# MicroPlayerSCH.net
KiCad netlist of a schematic drawn in Altium Designer
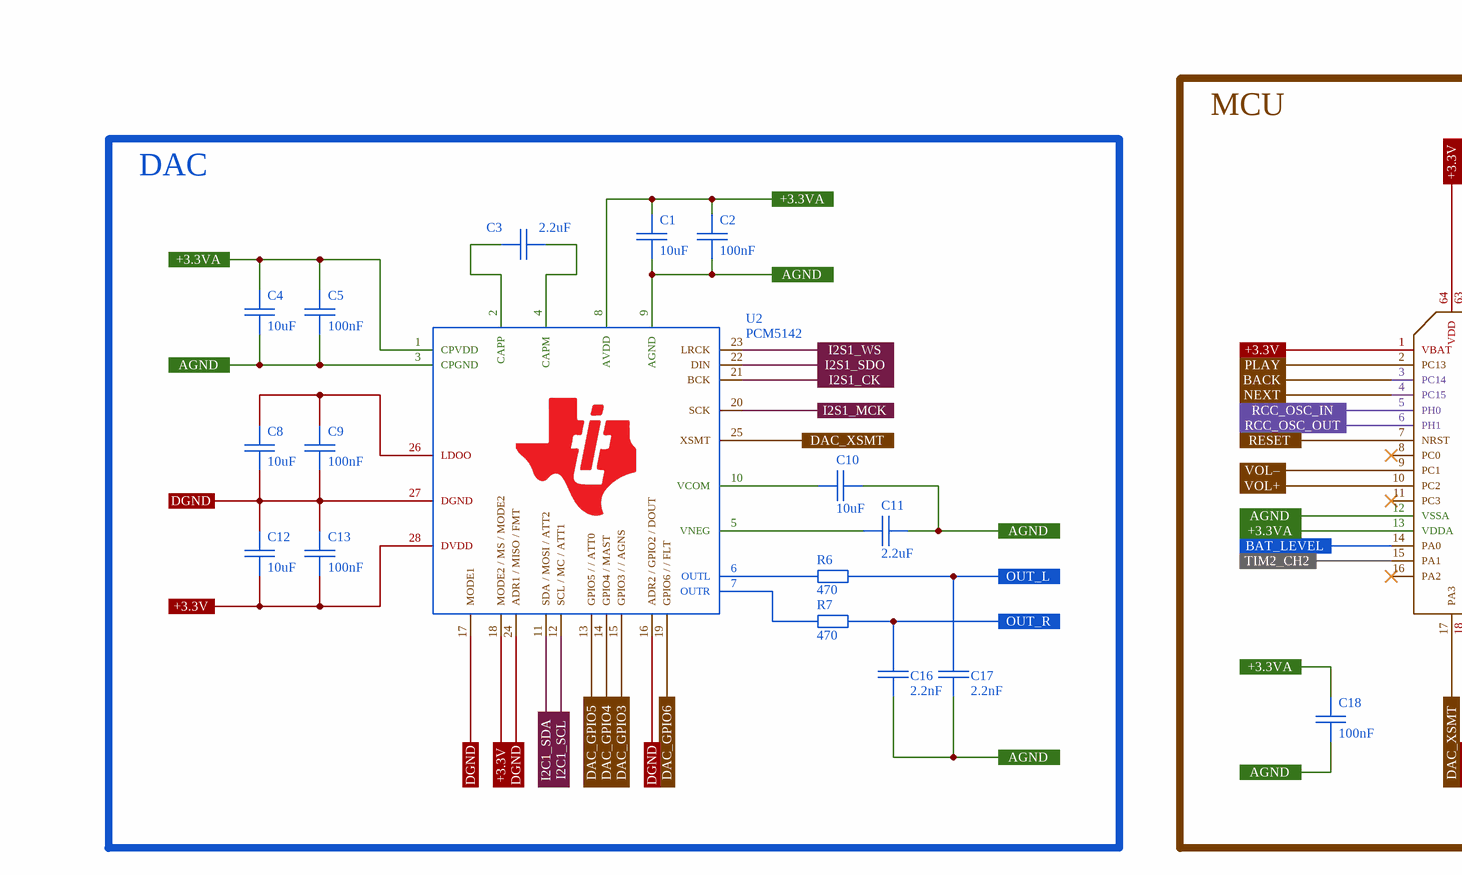
[diagram p0: MicroPlayerSCH.SchDoc, top left]
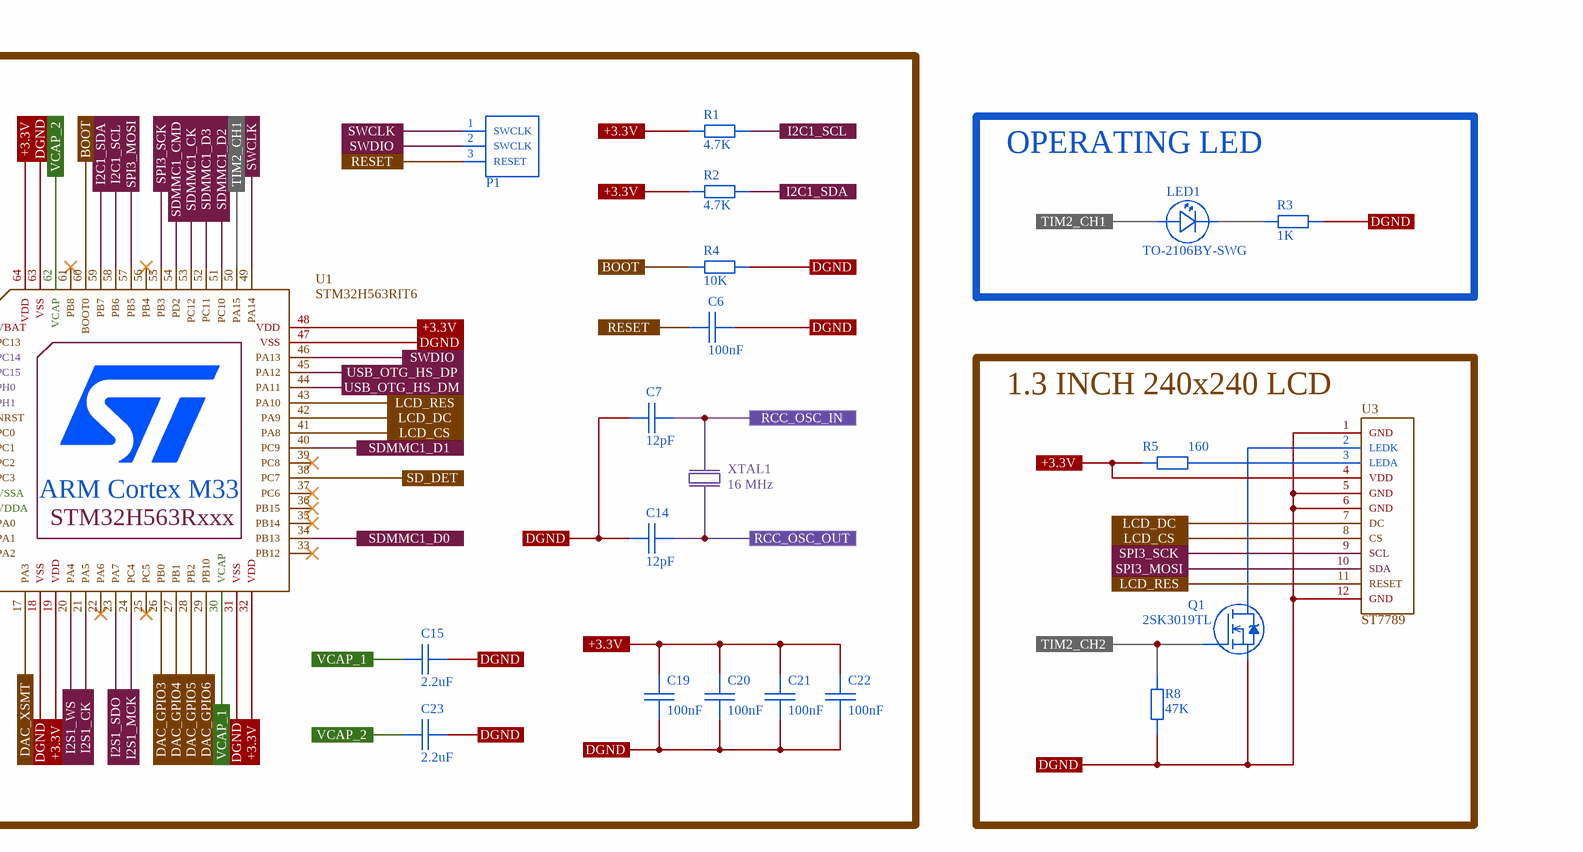
[diagram p1: MicroPlayerSCH.SchDoc, top right]
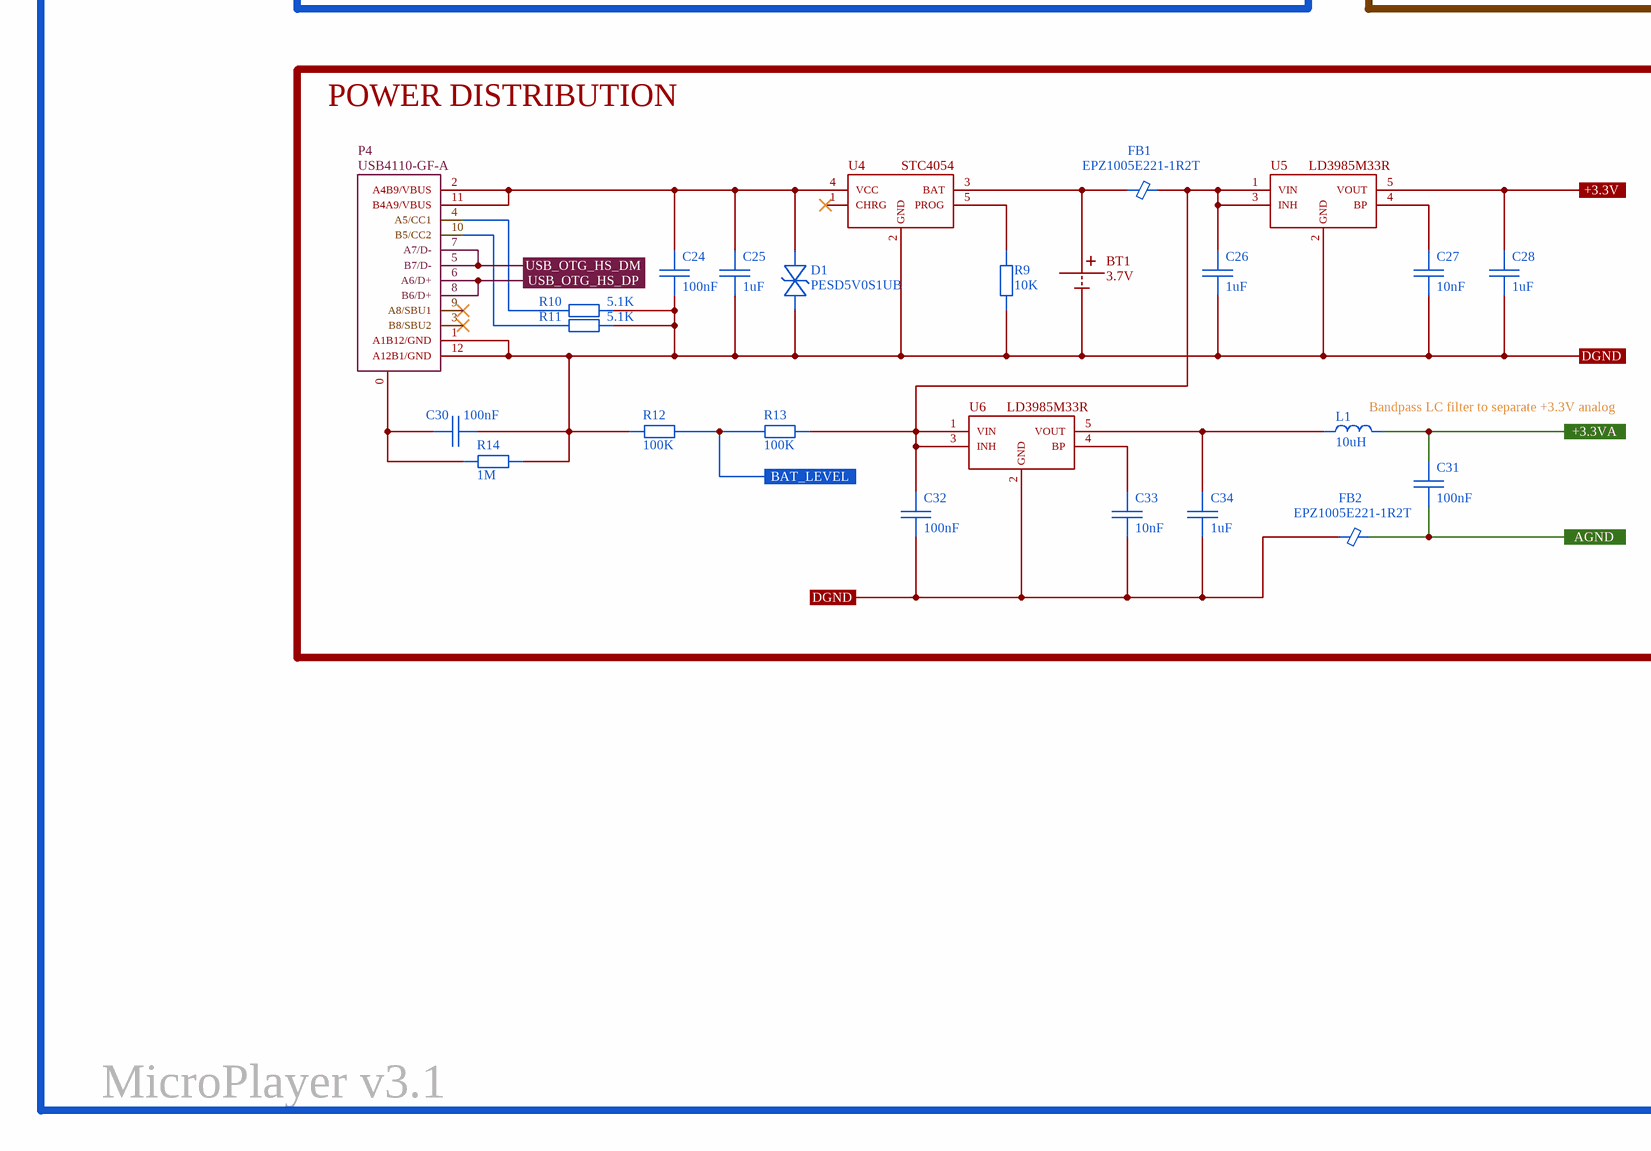
[diagram p2: MicroPlayerSCH.SchDoc, bottom left]
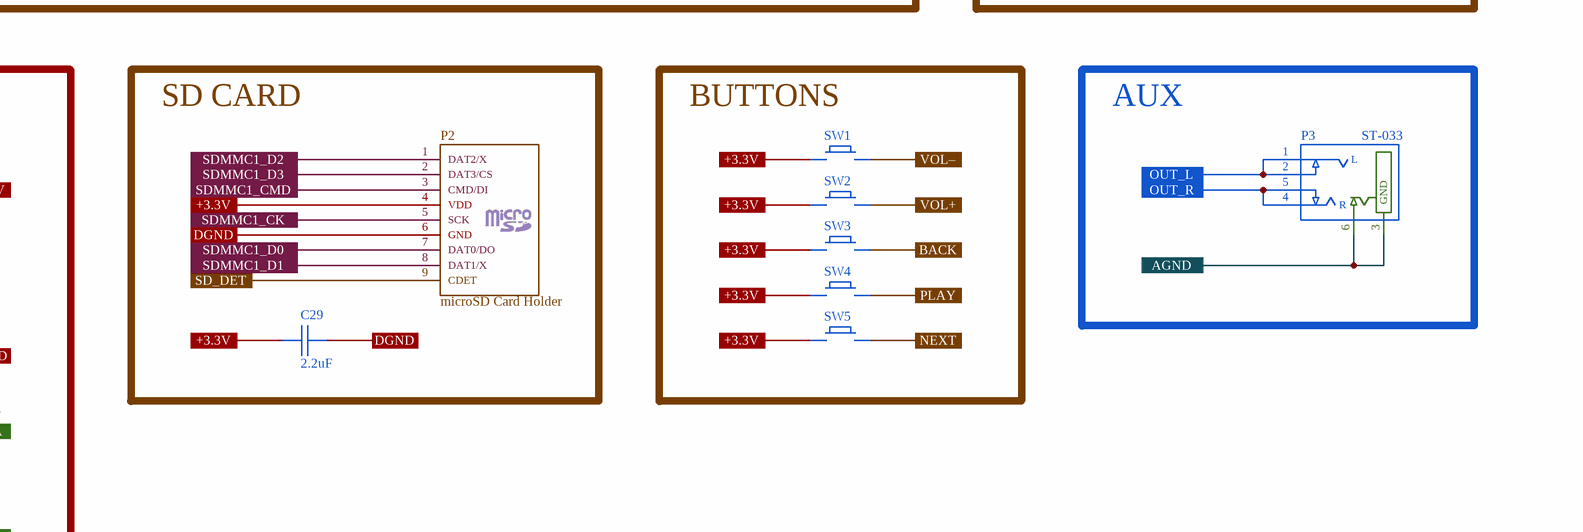
[diagram p3: MicroPlayerSCH.SchDoc, bottom right]

(export (version "E")
  (design (tool "Eeschema 10.0.6"))
  (components
    (comp (ref "BT1") (value "3.7V") (footprint "_2-PAD-SM") (libsource (lib "PowerUnits") (part "Battery")))
    (comp (ref "C1")
      (value "10uF")
      (footprint "C0402")
      (fields (field (name "VOLTAGE") "250V") (field (name "TOLERANCE") "5%"))
      (libsource (lib "CommonElements") (part "Cap"))
    )
    (comp (ref "C2")
      (value "100nF")
      (footprint "C0402")
      (fields (field (name "VOLTAGE") "250V") (field (name "TOLERANCE") "5%"))
      (libsource (lib "CommonElements") (part "Cap"))
    )
    (comp (ref "C3")
      (value "2.2uF")
      (footprint "C0402")
      (fields (field (name "VOLTAGE") "250V") (field (name "TOLERANCE") "5%"))
      (libsource (lib "CommonElements") (part "Cap"))
    )
    (comp (ref "C4")
      (value "10uF")
      (footprint "C0402")
      (fields (field (name "VOLTAGE") "250V") (field (name "TOLERANCE") "5%"))
      (libsource (lib "CommonElements") (part "Cap"))
    )
    (comp (ref "C5")
      (value "100nF")
      (footprint "C0402")
      (fields (field (name "VOLTAGE") "250V") (field (name "TOLERANCE") "5%"))
      (libsource (lib "CommonElements") (part "Cap"))
    )
    (comp (ref "C6")
      (value "100nF")
      (footprint "C0402")
      (fields (field (name "VOLTAGE") "250V") (field (name "TOLERANCE") "5%"))
      (libsource (lib "CommonElements") (part "Cap"))
    )
    (comp (ref "C7")
      (value "12pF")
      (footprint "C0402")
      (fields (field (name "VOLTAGE") "250V") (field (name "TOLERANCE") "5%"))
      (libsource (lib "CommonElements") (part "Cap"))
    )
    (comp (ref "C8")
      (value "10uF")
      (footprint "C0402")
      (fields (field (name "VOLTAGE") "250V") (field (name "TOLERANCE") "5%"))
      (libsource (lib "CommonElements") (part "Cap"))
    )
    (comp (ref "C9")
      (value "100nF")
      (footprint "C0402")
      (fields (field (name "VOLTAGE") "250V") (field (name "TOLERANCE") "5%"))
      (libsource (lib "CommonElements") (part "Cap"))
    )
    (comp (ref "C10")
      (value "10uF")
      (footprint "C0402")
      (fields (field (name "VOLTAGE") "250V") (field (name "TOLERANCE") "5%"))
      (libsource (lib "CommonElements") (part "Cap"))
    )
    (comp (ref "C11")
      (value "2.2uF")
      (footprint "C0402")
      (fields (field (name "VOLTAGE") "250V") (field (name "TOLERANCE") "5%"))
      (libsource (lib "CommonElements") (part "Cap"))
    )
    (comp (ref "C12")
      (value "10uF")
      (footprint "C0402")
      (fields (field (name "VOLTAGE") "250V") (field (name "TOLERANCE") "5%"))
      (libsource (lib "CommonElements") (part "Cap"))
    )
    (comp (ref "C13")
      (value "100nF")
      (footprint "C0402")
      (fields (field (name "VOLTAGE") "250V") (field (name "TOLERANCE") "5%"))
      (libsource (lib "CommonElements") (part "Cap"))
    )
    (comp (ref "C14")
      (value "12pF")
      (footprint "C0402")
      (fields (field (name "VOLTAGE") "250V") (field (name "TOLERANCE") "5%"))
      (libsource (lib "CommonElements") (part "Cap"))
    )
    (comp (ref "C15")
      (value "2.2uF")
      (footprint "C0402")
      (fields (field (name "VOLTAGE") "250V") (field (name "TOLERANCE") "5%"))
      (libsource (lib "CommonElements") (part "Cap"))
    )
    (comp (ref "C16")
      (value "2.2nF")
      (footprint "C0402")
      (fields (field (name "VOLTAGE") "250V") (field (name "TOLERANCE") "5%"))
      (libsource (lib "CommonElements") (part "Cap"))
    )
    (comp (ref "C17")
      (value "2.2nF")
      (footprint "C0402")
      (fields (field (name "VOLTAGE") "250V") (field (name "TOLERANCE") "5%"))
      (libsource (lib "CommonElements") (part "Cap"))
    )
    (comp (ref "C18")
      (value "100nF")
      (footprint "C0402")
      (fields (field (name "VOLTAGE") "250V") (field (name "TOLERANCE") "5%"))
      (libsource (lib "CommonElements") (part "Cap"))
    )
    (comp (ref "C19")
      (value "100nF")
      (footprint "C0402")
      (fields (field (name "VOLTAGE") "250V") (field (name "TOLERANCE") "5%"))
      (libsource (lib "CommonElements") (part "Cap"))
    )
    (comp (ref "C20")
      (value "100nF")
      (footprint "C0402")
      (fields (field (name "VOLTAGE") "250V") (field (name "TOLERANCE") "5%"))
      (libsource (lib "CommonElements") (part "Cap"))
    )
    (comp (ref "C21")
      (value "100nF")
      (footprint "C0402")
      (fields (field (name "VOLTAGE") "250V") (field (name "TOLERANCE") "5%"))
      (libsource (lib "CommonElements") (part "Cap"))
    )
    (comp (ref "C22")
      (value "100nF")
      (footprint "C0402")
      (fields (field (name "VOLTAGE") "250V") (field (name "TOLERANCE") "5%"))
      (libsource (lib "CommonElements") (part "Cap"))
    )
    (comp (ref "C23")
      (value "2.2uF")
      (footprint "C0402")
      (fields (field (name "VOLTAGE") "250V") (field (name "TOLERANCE") "5%"))
      (libsource (lib "CommonElements") (part "Cap"))
    )
    (comp (ref "C24")
      (value "100nF")
      (footprint "C0402")
      (fields (field (name "VOLTAGE") "250V") (field (name "TOLERANCE") "5%"))
      (libsource (lib "CommonElements") (part "Cap"))
    )
    (comp (ref "C25")
      (value "1uF")
      (footprint "C0402")
      (fields (field (name "VOLTAGE") "250V") (field (name "TOLERANCE") "5%"))
      (libsource (lib "CommonElements") (part "Cap"))
    )
    (comp (ref "C26")
      (value "1uF")
      (footprint "C0402")
      (fields (field (name "VOLTAGE") "250V") (field (name "TOLERANCE") "5%"))
      (libsource (lib "CommonElements") (part "Cap"))
    )
    (comp (ref "C27")
      (value "10nF")
      (footprint "C0402")
      (fields (field (name "VOLTAGE") "250V") (field (name "TOLERANCE") "5%"))
      (libsource (lib "CommonElements") (part "Cap"))
    )
    (comp (ref "C28")
      (value "1uF")
      (footprint "C0402")
      (fields (field (name "VOLTAGE") "250V") (field (name "TOLERANCE") "5%"))
      (libsource (lib "CommonElements") (part "Cap"))
    )
    (comp (ref "C29")
      (value "2.2uF")
      (footprint "C0402")
      (fields (field (name "VOLTAGE") "250V") (field (name "TOLERANCE") "5%"))
      (libsource (lib "CommonElements") (part "Cap"))
    )
    (comp (ref "C30")
      (value "100nF")
      (footprint "C0402")
      (fields (field (name "VOLTAGE") "250V") (field (name "TOLERANCE") "5%"))
      (libsource (lib "CommonElements") (part "Cap"))
    )
    (comp (ref "C31")
      (value "100nF")
      (footprint "C0402")
      (fields (field (name "VOLTAGE") "250V") (field (name "TOLERANCE") "5%"))
      (libsource (lib "CommonElements") (part "Cap"))
    )
    (comp (ref "C32")
      (value "100nF")
      (footprint "C0402")
      (fields (field (name "VOLTAGE") "250V") (field (name "TOLERANCE") "5%"))
      (libsource (lib "CommonElements") (part "Cap"))
    )
    (comp (ref "C33")
      (value "10nF")
      (footprint "C0402")
      (fields (field (name "VOLTAGE") "250V") (field (name "TOLERANCE") "5%"))
      (libsource (lib "CommonElements") (part "Cap"))
    )
    (comp (ref "C34")
      (value "1uF")
      (footprint "C0402")
      (fields (field (name "VOLTAGE") "250V") (field (name "TOLERANCE") "5%"))
      (libsource (lib "CommonElements") (part "Cap"))
    )
    (comp (ref "D1")
      (value "PESD5V0S1UB")
      (footprint "SOD-523")
      (libsource (lib "CommonElements") (part "Suppressor"))
    )
    (comp (ref "FB1")
      (value "EPZ1005E221-1R2T")
      (footprint "L0402")
      (libsource (lib "CommonElements") (part "Ferrite Bead"))
    )
    (comp (ref "FB2")
      (value "EPZ1005E221-1R2T")
      (footprint "L0402")
      (libsource (lib "CommonElements") (part "Ferrite Bead"))
    )
    (comp (ref "L1")
      (value "10uH")
      (footprint "L0603")
      (fields (field (name "TOLERANCE") "30%") (field (name "PART NUMBER") "LQM21FN100N00K"))
      (libsource (lib "CommonElements") (part "Inductor"))
    )
    (comp (ref "LED1")
      (value "TO-2106BY-SWG")
      (footprint "LED-2106-R/A")
      (libsource (lib "CommonElements") (part "LED"))
    )
    (comp (ref "P1") (value "P3") (footprint "_3-PAD-SM") (libsource (lib "Connectors") (part "P3")))
    (comp (ref "P2")
      (value "microSD Card Holder")
      (footprint "L-KLS1-TF-003")
      (libsource (lib "Connectors") (part "MicroSD-CD1"))
    )
    (comp (ref "P3")
      (value "ST-033")
      (footprint "_3-PAD-TH")
      (libsource (lib "Connectors") (part "AJack Socket Stereo"))
    )
    (comp (ref "P4")
      (value "USB4110-GF-A")
      (footprint "USB-TYPE-C")
      (libsource (lib "Connectors") (part "USB Type C with 0"))
    )
    (comp (ref "Q1")
      (value "2SK3019TL")
      (footprint "SOT-416FL")
      (libsource (lib "CommonElements") (part "MOSFET-N"))
    )
    (comp (ref "R1")
      (value "4.7K")
      (footprint "R0402")
      (fields (field (name "TOLERANCE") "5%") (field (name "POWER") "0.125W"))
      (libsource (lib "CommonElements") (part "Res"))
    )
    (comp (ref "R2")
      (value "4.7K")
      (footprint "R0402")
      (fields (field (name "TOLERANCE") "5%") (field (name "POWER") "0.125W"))
      (libsource (lib "CommonElements") (part "Res"))
    )
    (comp (ref "R3")
      (value "1K")
      (footprint "R0402")
      (fields (field (name "TOLERANCE") "5%") (field (name "POWER") "0.125W"))
      (libsource (lib "CommonElements") (part "Res"))
    )
    (comp (ref "R4")
      (value "10K")
      (footprint "R0402")
      (fields (field (name "TOLERANCE") "5%") (field (name "POWER") "0.125W"))
      (libsource (lib "CommonElements") (part "Res"))
    )
    (comp (ref "R5")
      (value "160")
      (footprint "R0402")
      (fields (field (name "TOLERANCE") "5%") (field (name "POWER") "0.125W"))
      (libsource (lib "CommonElements") (part "Res"))
    )
    (comp (ref "R6")
      (value "470")
      (footprint "R0402")
      (fields (field (name "TOLERANCE") "5%") (field (name "POWER") "0.125W"))
      (libsource (lib "CommonElements") (part "Res"))
    )
    (comp (ref "R7")
      (value "470")
      (footprint "R0402")
      (fields (field (name "TOLERANCE") "5%") (field (name "POWER") "0.125W"))
      (libsource (lib "CommonElements") (part "Res"))
    )
    (comp (ref "R8")
      (value "47K")
      (footprint "R0402")
      (fields (field (name "TOLERANCE") "5%") (field (name "POWER") "0.125W"))
      (libsource (lib "CommonElements") (part "Res"))
    )
    (comp (ref "R9")
      (value "10K")
      (footprint "R0402")
      (fields (field (name "TOLERANCE") "5%") (field (name "POWER") "0.125W"))
      (libsource (lib "CommonElements") (part "Res"))
    )
    (comp (ref "R10")
      (value "5.1K")
      (footprint "R0402")
      (fields (field (name "TOLERANCE") "5%") (field (name "POWER") "0.125W"))
      (libsource (lib "CommonElements") (part "Res"))
    )
    (comp (ref "R11")
      (value "5.1K")
      (footprint "R0402")
      (fields (field (name "TOLERANCE") "5%") (field (name "POWER") "0.125W"))
      (libsource (lib "CommonElements") (part "Res"))
    )
    (comp (ref "R12")
      (value "100K")
      (footprint "R0402")
      (fields (field (name "TOLERANCE") "5%") (field (name "POWER") "0.125W"))
      (libsource (lib "CommonElements") (part "Res"))
    )
    (comp (ref "R13")
      (value "100K")
      (footprint "R0402")
      (fields (field (name "TOLERANCE") "5%") (field (name "POWER") "0.125W"))
      (libsource (lib "CommonElements") (part "Res"))
    )
    (comp (ref "R14")
      (value "1M")
      (footprint "R0402")
      (fields (field (name "TOLERANCE") "5%") (field (name "POWER") "0.125W"))
      (libsource (lib "CommonElements") (part "Res"))
    )
    (comp (ref "SW1")
      (value "~")
      (footprint "BUT-SMD-4X3.5X2MM")
      (libsource (lib "CommonElements") (part "Button"))
    )
    (comp (ref "SW2")
      (value "~")
      (footprint "BUT-SMD-4X3.5X2MM")
      (libsource (lib "CommonElements") (part "Button"))
    )
    (comp (ref "SW3")
      (value "~")
      (footprint "BUT-SMD-4X3.5X2MM")
      (libsource (lib "CommonElements") (part "Button"))
    )
    (comp (ref "SW4")
      (value "~")
      (footprint "BUT-SMD-4X3.5X2MM")
      (libsource (lib "CommonElements") (part "Button"))
    )
    (comp (ref "SW5")
      (value "~")
      (footprint "BUT-SMD-4X3.5X2MM")
      (libsource (lib "CommonElements") (part "Button"))
    )
    (comp (ref "U1")
      (value "STM32H563RIT6")
      (footprint "LQFP64")
      (libsource (lib "STM32") (part "STM32H563Rxxx"))
    )
    (comp (ref "U2")
      (value "PCM5142")
      (footprint "TSSOP28")
      (description "2-VRMS DirectPath™, 112/106-dB Audio Stereo DAC With 32-bit, 384-kHz PCM Interface")
      (libsource (lib "Miscellaneous") (part "PCM514x"))
    )
    (comp (ref "U3")
      (value "ST7789")
      (footprint "1.3INCH_LCD_WELDED")
      (description "135x240 Display")
      (libsource (lib "Modules") (part "1.3inch TFT LCD 12-pin"))
    )
    (comp (ref "U4")
      (value "STC4054")
      (footprint "SOT-23-5")
      (description "800mA Standalone linear Li-Ion Battery charger with thermal regulation")
      (libsource (lib "PowerUnits") (part "STC4054"))
    )
    (comp (ref "U5")
      (value "LD3985M33R")
      (footprint "SOT-23-5")
      (description "Ultra low drop and low noise BiCMOS voltage regulators, 150 mA")
      (libsource (lib "PowerUnits") (part "LD3985"))
    )
    (comp (ref "U6")
      (value "LD3985M33R")
      (footprint "SOT-23-5")
      (description "Ultra low drop and low noise BiCMOS voltage regulators, 150 mA")
      (libsource (lib "PowerUnits") (part "LD3985"))
    )
    (comp (ref "XTAL1")
      (value "16 MHz")
      (footprint "7U")
      (fields (field (name "TOLERANCE") "0.001%"))
      (libsource (lib "CommonElements") (part "Crystal"))
    )
  )
  (nets
    (net (code "1") (name "/+3.3V") (class "Default")
      (node (ref "C12") (pin "2") (pintype "passive"))
      (node (ref "C13") (pin "2") (pintype "passive"))
      (node (ref "C19") (pin "2") (pintype "passive"))
      (node (ref "C20") (pin "2") (pintype "passive"))
      (node (ref "C21") (pin "2") (pintype "passive"))
      (node (ref "C22") (pin "2") (pintype "passive"))
      (node (ref "C28") (pin "2") (pintype "passive"))
      (node (ref "C29") (pin "1") (pintype "passive"))
      (node (ref "P2") (pin "4") (pinfunction "VDD_4") (pintype "passive"))
      (node (ref "R1") (pin "1") (pintype "passive"))
      (node (ref "R2") (pin "1") (pintype "passive"))
      (node (ref "R5") (pin "1") (pintype "passive"))
      (node (ref "SW1") (pin "1") (pintype "passive"))
      (node (ref "SW2") (pin "1") (pintype "passive"))
      (node (ref "SW3") (pin "1") (pintype "passive"))
      (node (ref "SW4") (pin "1") (pintype "passive"))
      (node (ref "SW5") (pin "1") (pintype "passive"))
      (node (ref "U1") (pin "1") (pinfunction "VBAT_1") (pintype "passive"))
      (node (ref "U1") (pin "19") (pinfunction "VDD_19") (pintype "passive"))
      (node (ref "U1") (pin "32") (pinfunction "VDD_32") (pintype "passive"))
      (node (ref "U1") (pin "48") (pinfunction "VDD_48") (pintype "passive"))
      (node (ref "U1") (pin "64") (pinfunction "VDD_64") (pintype "passive"))
      (node (ref "U2") (pin "18") (pinfunction "MODE2_/_MS_/_MODE2_18") (pintype "passive"))
      (node (ref "U2") (pin "28") (pinfunction "DVDD_28") (pintype "passive"))
      (node (ref "U3") (pin "4") (pinfunction "VDD_4") (pintype "passive"))
      (node (ref "U5") (pin "5") (pinfunction "VOUT_5") (pintype "passive"))
    )
    (net (code "2") (name "/+3.3VA") (class "Default")
      (node (ref "C1") (pin "1") (pintype "passive"))
      (node (ref "C18") (pin "2") (pintype "passive"))
      (node (ref "C2") (pin "1") (pintype "passive"))
      (node (ref "C31") (pin "1") (pintype "passive"))
      (node (ref "C4") (pin "1") (pintype "passive"))
      (node (ref "C5") (pin "1") (pintype "passive"))
      (node (ref "L1") (pin "2") (pintype "passive"))
      (node (ref "U1") (pin "13") (pinfunction "VDDA_13") (pintype "passive"))
      (node (ref "U2") (pin "1") (pinfunction "CPVDD_1") (pintype "passive"))
      (node (ref "U2") (pin "8") (pinfunction "AVDD_8") (pintype "passive"))
    )
    (net (code "3") (name "/AGND") (class "Default")
      (node (ref "C1") (pin "2") (pintype "passive"))
      (node (ref "C10") (pin "2") (pintype "passive"))
      (node (ref "C11") (pin "2") (pintype "passive"))
      (node (ref "C16") (pin "1") (pintype "passive"))
      (node (ref "C17") (pin "1") (pintype "passive"))
      (node (ref "C18") (pin "1") (pintype "passive"))
      (node (ref "C2") (pin "2") (pintype "passive"))
      (node (ref "C31") (pin "2") (pintype "passive"))
      (node (ref "C4") (pin "2") (pintype "passive"))
      (node (ref "C5") (pin "2") (pintype "passive"))
      (node (ref "FB2") (pin "2") (pintype "passive"))
      (node (ref "P3") (pin "3") (pinfunction "GND_3") (pintype "passive"))
      (node (ref "P3") (pin "6") (pintype "passive"))
      (node (ref "U1") (pin "12") (pinfunction "VSSA_12") (pintype "passive"))
      (node (ref "U2") (pin "3") (pinfunction "CPGND_3") (pintype "passive"))
      (node (ref "U2") (pin "9") (pinfunction "AGND_9") (pintype "passive"))
    )
    (net (code "4") (name "/BACK") (class "Default")
      (node (ref "SW3") (pin "2") (pintype "passive"))
      (node (ref "U1") (pin "3") (pinfunction "PC14_3") (pintype "passive"))
    )
    (net (code "5") (name "/BAT_LEVEL") (class "Default")
      (node (ref "R12") (pin "1") (pintype "passive"))
      (node (ref "R13") (pin "2") (pintype "passive"))
      (node (ref "U1") (pin "14") (pinfunction "PA0_14") (pintype "passive"))
    )
    (net (code "6") (name "/BOOT") (class "Default")
      (node (ref "R4") (pin "1") (pintype "passive"))
      (node (ref "U1") (pin "60") (pinfunction "BOOT0_60") (pintype "passive"))
    )
    (net (code "7") (name "/DAC_GPIO3") (class "Default")
      (node (ref "U1") (pin "26") (pinfunction "PB0_26") (pintype "passive"))
      (node (ref "U2") (pin "15") (pinfunction "GPIO3_/_/_AGNS_15") (pintype "passive"))
    )
    (net (code "8") (name "/DAC_GPIO4") (class "Default")
      (node (ref "U1") (pin "27") (pinfunction "PB1_27") (pintype "passive"))
      (node (ref "U2") (pin "14") (pinfunction "GPIO4_/_MAST_14") (pintype "passive"))
    )
    (net (code "9") (name "/DAC_GPIO5") (class "Default")
      (node (ref "U1") (pin "28") (pinfunction "PB2_28") (pintype "passive"))
      (node (ref "U2") (pin "13") (pinfunction "GPIO5_/_/_ATT0_13") (pintype "passive"))
    )
    (net (code "10") (name "/DAC_GPIO6") (class "Default")
      (node (ref "U1") (pin "29") (pinfunction "PB10_29") (pintype "passive"))
      (node (ref "U2") (pin "19") (pinfunction "GPIO6_/_/_FLT_19") (pintype "passive"))
    )
    (net (code "11") (name "/DAC_XSMT") (class "Default")
      (node (ref "U1") (pin "17") (pinfunction "PA3_17") (pintype "passive"))
      (node (ref "U2") (pin "25") (pinfunction "XSMT_25") (pintype "passive"))
    )
    (net (code "12") (name "/DGND") (class "Default")
      (node (ref "BT1") (pin "2") (pintype "passive"))
      (node (ref "C12") (pin "1") (pintype "passive"))
      (node (ref "C13") (pin "1") (pintype "passive"))
      (node (ref "C14") (pin "2") (pintype "passive"))
      (node (ref "C15") (pin "1") (pintype "passive"))
      (node (ref "C19") (pin "1") (pintype "passive"))
      (node (ref "C20") (pin "1") (pintype "passive"))
      (node (ref "C21") (pin "1") (pintype "passive"))
      (node (ref "C22") (pin "1") (pintype "passive"))
      (node (ref "C23") (pin "1") (pintype "passive"))
      (node (ref "C24") (pin "1") (pintype "passive"))
      (node (ref "C25") (pin "2") (pintype "passive"))
      (node (ref "C26") (pin "1") (pintype "passive"))
      (node (ref "C27") (pin "1") (pintype "passive"))
      (node (ref "C28") (pin "1") (pintype "passive"))
      (node (ref "C29") (pin "2") (pintype "passive"))
      (node (ref "C30") (pin "1") (pintype "passive"))
      (node (ref "C32") (pin "1") (pintype "passive"))
      (node (ref "C33") (pin "1") (pintype "passive"))
      (node (ref "C34") (pin "1") (pintype "passive"))
      (node (ref "C6") (pin "1") (pintype "passive"))
      (node (ref "C7") (pin "2") (pintype "passive"))
      (node (ref "C8") (pin "2") (pintype "passive"))
      (node (ref "C9") (pin "2") (pintype "passive"))
      (node (ref "D1") (pin "1") (pintype "passive"))
      (node (ref "FB2") (pin "1") (pintype "passive"))
      (node (ref "P2") (pin "6") (pinfunction "GND_6") (pintype "passive"))
      (node (ref "P4") (pin "1") (pinfunction "A1B12/GND_1") (pintype "passive"))
      (node (ref "P4") (pin "12") (pinfunction "A12B1/GND_12") (pintype "passive"))
      (node (ref "Q1") (pin "2") (pinfunction "S_2") (pintype "passive"))
      (node (ref "R10") (pin "1") (pintype "passive"))
      (node (ref "R11") (pin "1") (pintype "passive"))
      (node (ref "R12") (pin "2") (pintype "passive"))
      (node (ref "R14") (pin "1") (pintype "passive"))
      (node (ref "R3") (pin "1") (pintype "passive"))
      (node (ref "R4") (pin "2") (pintype "passive"))
      (node (ref "R8") (pin "1") (pintype "passive"))
      (node (ref "R9") (pin "1") (pintype "passive"))
      (node (ref "U1") (pin "18") (pinfunction "VSS_18") (pintype "passive"))
      (node (ref "U1") (pin "31") (pinfunction "VSS_31") (pintype "passive"))
      (node (ref "U1") (pin "47") (pinfunction "VSS_47") (pintype "passive"))
      (node (ref "U1") (pin "63") (pinfunction "VSS_63") (pintype "passive"))
      (node (ref "U2") (pin "16") (pinfunction "ADR2_/_GPIO2_/_DOUT_16") (pintype "passive"))
      (node (ref "U2") (pin "17") (pinfunction "MODE1_17") (pintype "passive"))
      (node (ref "U2") (pin "24") (pinfunction "ADR1_/_MISO_/_FMT_24") (pintype "passive"))
      (node (ref "U2") (pin "27") (pinfunction "DGND_27") (pintype "passive"))
      (node (ref "U3") (pin "1") (pinfunction "GND_1") (pintype "passive"))
      (node (ref "U3") (pin "12") (pinfunction "GND_12") (pintype "passive"))
      (node (ref "U3") (pin "5") (pinfunction "GND_5") (pintype "passive"))
      (node (ref "U3") (pin "6") (pinfunction "GND_6") (pintype "passive"))
      (node (ref "U4") (pin "2") (pinfunction "GND_2") (pintype "passive"))
      (node (ref "U5") (pin "2") (pinfunction "GND_2") (pintype "passive"))
      (node (ref "U6") (pin "2") (pinfunction "GND_2") (pintype "passive"))
    )
    (net (code "13") (name "/I2C1_SCL") (class "Default")
      (node (ref "R1") (pin "2") (pintype "passive"))
      (node (ref "U1") (pin "58") (pinfunction "PB6_58") (pintype "passive"))
      (node (ref "U2") (pin "12") (pinfunction "SCL_/_MC_/_ATT1_12") (pintype "passive"))
    )
    (net (code "14") (name "/I2C1_SDA") (class "Default")
      (node (ref "R2") (pin "2") (pintype "passive"))
      (node (ref "U1") (pin "59") (pinfunction "PB7_59") (pintype "passive"))
      (node (ref "U2") (pin "11") (pinfunction "SDA_/_MOSI_/_ATT2_11") (pintype "passive"))
    )
    (net (code "15") (name "/I2S1_CK") (class "Default")
      (node (ref "U1") (pin "21") (pinfunction "PA5_21") (pintype "passive"))
      (node (ref "U2") (pin "21") (pinfunction "BCK_21") (pintype "passive"))
    )
    (net (code "16") (name "/I2S1_MCK") (class "Default")
      (node (ref "U1") (pin "24") (pinfunction "PC4_24") (pintype "passive"))
      (node (ref "U2") (pin "20") (pinfunction "SCK_20") (pintype "passive"))
    )
    (net (code "17") (name "/I2S1_SDO") (class "Default")
      (node (ref "U1") (pin "23") (pinfunction "PA7_23") (pintype "passive"))
      (node (ref "U2") (pin "22") (pinfunction "DIN_22") (pintype "passive"))
    )
    (net (code "18") (name "/I2S1_WS") (class "Default")
      (node (ref "U1") (pin "20") (pinfunction "PA4_20") (pintype "passive"))
      (node (ref "U2") (pin "23") (pinfunction "LRCK_23") (pintype "passive"))
    )
    (net (code "19") (name "/LCD_CS") (class "Default")
      (node (ref "U1") (pin "41") (pinfunction "PA8_41") (pintype "passive"))
      (node (ref "U3") (pin "8") (pinfunction "CS_8") (pintype "passive"))
    )
    (net (code "20") (name "/LCD_DC") (class "Default")
      (node (ref "U1") (pin "42") (pinfunction "PA9_42") (pintype "passive"))
      (node (ref "U3") (pin "7") (pinfunction "DC_7") (pintype "passive"))
    )
    (net (code "21") (name "/LCD_RES") (class "Default")
      (node (ref "U1") (pin "43") (pinfunction "PA10_43") (pintype "passive"))
      (node (ref "U3") (pin "11") (pinfunction "RESET_11") (pintype "passive"))
    )
    (net (code "22") (name "/NEXT") (class "Default")
      (node (ref "SW5") (pin "2") (pintype "passive"))
      (node (ref "U1") (pin "4") (pinfunction "PC15_4") (pintype "passive"))
    )
    (net (code "23") (name "/OUT_L") (class "Default")
      (node (ref "C17") (pin "2") (pintype "passive"))
      (node (ref "P3") (pin "1") (pinfunction "L_1") (pintype "passive"))
      (node (ref "P3") (pin "2") (pintype "passive"))
      (node (ref "R6") (pin "1") (pintype "passive"))
    )
    (net (code "24") (name "/OUT_R") (class "Default")
      (node (ref "C16") (pin "2") (pintype "passive"))
      (node (ref "P3") (pin "4") (pinfunction "R_4") (pintype "passive"))
      (node (ref "P3") (pin "5") (pintype "passive"))
      (node (ref "R7") (pin "1") (pintype "passive"))
    )
    (net (code "25") (name "/PLAY") (class "Default")
      (node (ref "SW4") (pin "2") (pintype "passive"))
      (node (ref "U1") (pin "2") (pinfunction "PC13_2") (pintype "passive"))
    )
    (net (code "26") (name "/RCC_OSC_IN") (class "Default")
      (node (ref "C7") (pin "1") (pintype "passive"))
      (node (ref "U1") (pin "5") (pinfunction "PH0_5") (pintype "passive"))
      (node (ref "XTAL1") (pin "1") (pintype "passive"))
    )
    (net (code "27") (name "/RCC_OSC_OUT") (class "Default")
      (node (ref "C14") (pin "1") (pintype "passive"))
      (node (ref "U1") (pin "6") (pinfunction "PH1_6") (pintype "passive"))
      (node (ref "XTAL1") (pin "2") (pintype "passive"))
    )
    (net (code "28") (name "/RESET") (class "Default")
      (node (ref "C6") (pin "2") (pintype "passive"))
      (node (ref "P1") (pin "3") (pinfunction "RESET_3") (pintype "passive"))
      (node (ref "U1") (pin "7") (pinfunction "NRST_7") (pintype "passive"))
    )
    (net (code "29") (name "/SDMMC1_CK") (class "Default")
      (node (ref "P2") (pin "5") (pinfunction "SCK_5") (pintype "passive"))
      (node (ref "U1") (pin "53") (pinfunction "PC12_53") (pintype "passive"))
    )
    (net (code "30") (name "/SDMMC1_CMD") (class "Default")
      (node (ref "P2") (pin "3") (pinfunction "CMD/DI_3") (pintype "passive"))
      (node (ref "U1") (pin "54") (pinfunction "PD2_54") (pintype "passive"))
    )
    (net (code "31") (name "/SDMMC1_D0") (class "Default")
      (node (ref "P2") (pin "7") (pinfunction "DAT0/DO_7") (pintype "passive"))
      (node (ref "U1") (pin "34") (pinfunction "PB13_34") (pintype "passive"))
    )
    (net (code "32") (name "/SDMMC1_D1") (class "Default")
      (node (ref "P2") (pin "8") (pinfunction "DAT1/X_8") (pintype "passive"))
      (node (ref "U1") (pin "40") (pinfunction "PC9_40") (pintype "passive"))
    )
    (net (code "33") (name "/SDMMC1_D2") (class "Default")
      (node (ref "P2") (pin "1") (pinfunction "DAT2/X_1") (pintype "passive"))
      (node (ref "U1") (pin "51") (pinfunction "PC10_51") (pintype "passive"))
    )
    (net (code "34") (name "/SDMMC1_D3") (class "Default")
      (node (ref "P2") (pin "2") (pinfunction "DAT3/CS_2") (pintype "passive"))
      (node (ref "U1") (pin "52") (pinfunction "PC11_52") (pintype "passive"))
    )
    (net (code "35") (name "/SD_DET") (class "Default")
      (node (ref "P2") (pin "9") (pinfunction "CDET_9") (pintype "passive"))
      (node (ref "U1") (pin "38") (pinfunction "PC7_38") (pintype "passive"))
    )
    (net (code "36") (name "/SPI3_MOSI") (class "Default")
      (node (ref "U1") (pin "57") (pinfunction "PB5_57") (pintype "passive"))
      (node (ref "U3") (pin "10") (pinfunction "SDA_10") (pintype "passive"))
    )
    (net (code "37") (name "/SPI3_SCK") (class "Default")
      (node (ref "U1") (pin "55") (pinfunction "PB3_55") (pintype "passive"))
      (node (ref "U3") (pin "9") (pinfunction "SCL_9") (pintype "passive"))
    )
    (net (code "38") (name "/SWCLK") (class "Default")
      (node (ref "P1") (pin "1") (pinfunction "SWCLK_1") (pintype "passive"))
      (node (ref "U1") (pin "49") (pinfunction "PA14_49") (pintype "passive"))
    )
    (net (code "39") (name "/SWDIO") (class "Default")
      (node (ref "P1") (pin "2") (pinfunction "SWCLK_2") (pintype "passive"))
      (node (ref "U1") (pin "46") (pinfunction "PA13_46") (pintype "passive"))
    )
    (net (code "40") (name "/TIM2_CH1") (class "Default")
      (node (ref "LED1") (pin "1") (pinfunction "Anode_1") (pintype "passive"))
      (node (ref "U1") (pin "50") (pinfunction "PA15_50") (pintype "passive"))
    )
    (net (code "41") (name "/TIM2_CH2") (class "Default")
      (node (ref "Q1") (pin "1") (pinfunction "G_1") (pintype "passive"))
      (node (ref "R8") (pin "2") (pintype "passive"))
      (node (ref "U1") (pin "15") (pinfunction "PA1_15") (pintype "passive"))
    )
    (net (code "42") (name "/USB_OTG_HS_DM") (class "Default")
      (node (ref "P4") (pin "5") (pinfunction "B7/D-_5") (pintype "passive"))
      (node (ref "P4") (pin "7") (pinfunction "A7/D-_7") (pintype "passive"))
      (node (ref "U1") (pin "44") (pinfunction "PA11_44") (pintype "passive"))
    )
    (net (code "43") (name "/USB_OTG_HS_DP") (class "Default")
      (node (ref "P4") (pin "6") (pinfunction "A6/D+_6") (pintype "passive"))
      (node (ref "P4") (pin "8") (pinfunction "B6/D+_8") (pintype "passive"))
      (node (ref "U1") (pin "45") (pinfunction "PA12_45") (pintype "passive"))
    )
    (net (code "44") (name "/VCAP_1") (class "Default")
      (node (ref "C15") (pin "2") (pintype "passive"))
      (node (ref "U1") (pin "30") (pinfunction "VCAP_30") (pintype "passive"))
    )
    (net (code "45") (name "/VCAP_2") (class "Default")
      (node (ref "C23") (pin "2") (pintype "passive"))
      (node (ref "U1") (pin "62") (pinfunction "VCAP_62") (pintype "passive"))
    )
    (net (code "46") (name "/VOL+") (class "Default")
      (node (ref "SW2") (pin "2") (pintype "passive"))
      (node (ref "U1") (pin "10") (pinfunction "PC2_10") (pintype "passive"))
    )
    (net (code "47") (name "/VOL–") (class "Default")
      (node (ref "SW1") (pin "2") (pintype "passive"))
      (node (ref "U1") (pin "9") (pinfunction "PC1_9") (pintype "passive"))
    )
    (net (code "48") (name "Net-(C30-Pad2)") (class "Default")
      (node (ref "C30") (pin "2") (pintype "passive"))
      (node (ref "P4") (pin "0") (pintype "passive"))
      (node (ref "R14") (pin "2") (pintype "passive"))
    )
    (net (code "49") (name "Net-(LED1-Cathode)") (class "Default")
      (node (ref "LED1") (pin "2") (pinfunction "Cathode_2") (pintype "passive"))
      (node (ref "R3") (pin "2") (pintype "passive"))
    )
    (net (code "50") (name "Net-(P4-A4B9{slash}VBUS)") (class "Default")
      (node (ref "C24") (pin "2") (pintype "passive"))
      (node (ref "C25") (pin "1") (pintype "passive"))
      (node (ref "D1") (pin "2") (pintype "passive"))
      (node (ref "P4") (pin "11") (pinfunction "B4A9/VBUS_11") (pintype "passive"))
      (node (ref "P4") (pin "2") (pinfunction "A4B9/VBUS_2") (pintype "passive"))
      (node (ref "U4") (pin "4") (pinfunction "VCC_4") (pintype "passive"))
    )
    (net (code "51") (name "Net-(P4-A5{slash}CC1)") (class "Default")
      (node (ref "P4") (pin "4") (pinfunction "A5/CC1_4") (pintype "passive"))
      (node (ref "R10") (pin "2") (pintype "passive"))
    )
    (net (code "52") (name "Net-(P4-B5{slash}CC2)") (class "Default")
      (node (ref "P4") (pin "10") (pinfunction "B5/CC2_10") (pintype "passive"))
      (node (ref "R11") (pin "2") (pintype "passive"))
    )
    (net (code "53") (name "Net-(Q1-D)") (class "Default")
      (node (ref "Q1") (pin "3") (pinfunction "D_3") (pintype "passive"))
      (node (ref "U3") (pin "2") (pinfunction "LEDK_2") (pintype "passive"))
    )
    (net (code "54") (name "Net-(U2-CAPM)") (class "Default")
      (node (ref "C3") (pin "2") (pintype "passive"))
      (node (ref "U2") (pin "4") (pinfunction "CAPM_4") (pintype "passive"))
    )
    (net (code "55") (name "Net-(U2-CAPP)") (class "Default")
      (node (ref "C3") (pin "1") (pintype "passive"))
      (node (ref "U2") (pin "2") (pinfunction "CAPP_2") (pintype "passive"))
    )
    (net (code "56") (name "Net-(U2-LDOO)") (class "Default")
      (node (ref "C8") (pin "1") (pintype "passive"))
      (node (ref "C9") (pin "1") (pintype "passive"))
      (node (ref "U2") (pin "26") (pinfunction "LDOO_26") (pintype "passive"))
    )
    (net (code "57") (name "Net-(U2-OUTL)") (class "Default")
      (node (ref "R6") (pin "2") (pintype "passive"))
      (node (ref "U2") (pin "6") (pinfunction "OUTL_6") (pintype "passive"))
    )
    (net (code "58") (name "Net-(U2-OUTR)") (class "Default")
      (node (ref "R7") (pin "2") (pintype "passive"))
      (node (ref "U2") (pin "7") (pinfunction "OUTR_7") (pintype "passive"))
    )
    (net (code "59") (name "Net-(U2-VCOM)") (class "Default")
      (node (ref "C10") (pin "1") (pintype "passive"))
      (node (ref "U2") (pin "10") (pinfunction "VCOM_10") (pintype "passive"))
    )
    (net (code "60") (name "Net-(U2-VNEG)") (class "Default")
      (node (ref "C11") (pin "1") (pintype "passive"))
      (node (ref "U2") (pin "5") (pinfunction "VNEG_5") (pintype "passive"))
    )
    (net (code "61") (name "Net-(U3-LEDA)") (class "Default")
      (node (ref "R5") (pin "2") (pintype "passive"))
      (node (ref "U3") (pin "3") (pinfunction "LEDA_3") (pintype "passive"))
    )
    (net (code "62") (name "Net-(U4-BAT)") (class "Default")
      (node (ref "BT1") (pin "1") (pintype "passive"))
      (node (ref "FB1") (pin "1") (pintype "passive"))
      (node (ref "U4") (pin "3") (pinfunction "BAT_3") (pintype "passive"))
    )
    (net (code "63") (name "Net-(U4-PROG)") (class "Default")
      (node (ref "R9") (pin "2") (pintype "passive"))
      (node (ref "U4") (pin "5") (pinfunction "PROG_5") (pintype "passive"))
    )
    (net (code "64") (name "Net-(U5-BP)") (class "Default")
      (node (ref "C27") (pin "2") (pintype "passive"))
      (node (ref "U5") (pin "4") (pinfunction "BP_4") (pintype "passive"))
    )
    (net (code "65") (name "Net-(U5-INH)") (class "Default")
      (node (ref "C26") (pin "2") (pintype "passive"))
      (node (ref "C32") (pin "2") (pintype "passive"))
      (node (ref "FB1") (pin "2") (pintype "passive"))
      (node (ref "R13") (pin "1") (pintype "passive"))
      (node (ref "U5") (pin "1") (pinfunction "VIN_1") (pintype "passive"))
      (node (ref "U5") (pin "3") (pinfunction "INH_3") (pintype "passive"))
      (node (ref "U6") (pin "1") (pinfunction "VIN_1") (pintype "passive"))
      (node (ref "U6") (pin "3") (pinfunction "INH_3") (pintype "passive"))
    )
    (net (code "66") (name "Net-(U6-BP)") (class "Default")
      (node (ref "C33") (pin "2") (pintype "passive"))
      (node (ref "U6") (pin "4") (pinfunction "BP_4") (pintype "passive"))
    )
    (net (code "67") (name "Net-(U6-VOUT)") (class "Default")
      (node (ref "C34") (pin "2") (pintype "passive"))
      (node (ref "L1") (pin "1") (pintype "passive"))
      (node (ref "U6") (pin "5") (pinfunction "VOUT_5") (pintype "passive"))
    )
    (net (code "68") (name "unconnected-(P4-A8{slash}SBU1-Pad9)") (class "Default")
      (node (ref "P4") (pin "9") (pinfunction "A8/SBU1_9") (pintype "passive+no_connect"))
    )
    (net (code "69") (name "unconnected-(P4-B8{slash}SBU2-Pad3)") (class "Default")
      (node (ref "P4") (pin "3") (pinfunction "B8/SBU2_3") (pintype "passive+no_connect"))
    )
    (net (code "70") (name "unconnected-(U1-PA2-Pad16)") (class "Default")
      (node (ref "U1") (pin "16") (pinfunction "PA2_16") (pintype "passive+no_connect"))
    )
    (net (code "71") (name "unconnected-(U1-PA6-Pad22)") (class "Default")
      (node (ref "U1") (pin "22") (pinfunction "PA6_22") (pintype "passive+no_connect"))
    )
    (net (code "72") (name "unconnected-(U1-PB4-Pad56)") (class "Default")
      (node (ref "U1") (pin "56") (pinfunction "PB4_56") (pintype "passive+no_connect"))
    )
    (net (code "73") (name "unconnected-(U1-PB8-Pad61)") (class "Default")
      (node (ref "U1") (pin "61") (pinfunction "PB8_61") (pintype "passive+no_connect"))
    )
    (net (code "74") (name "unconnected-(U1-PB12-Pad33)") (class "Default")
      (node (ref "U1") (pin "33") (pinfunction "PB12_33") (pintype "passive+no_connect"))
    )
    (net (code "75") (name "unconnected-(U1-PB14-Pad35)") (class "Default")
      (node (ref "U1") (pin "35") (pinfunction "PB14_35") (pintype "passive+no_connect"))
    )
    (net (code "76") (name "unconnected-(U1-PB15-Pad36)") (class "Default")
      (node (ref "U1") (pin "36") (pinfunction "PB15_36") (pintype "passive+no_connect"))
    )
    (net (code "77") (name "unconnected-(U1-PC0-Pad8)") (class "Default")
      (node (ref "U1") (pin "8") (pinfunction "PC0_8") (pintype "passive+no_connect"))
    )
    (net (code "78") (name "unconnected-(U1-PC3-Pad11)") (class "Default")
      (node (ref "U1") (pin "11") (pinfunction "PC3_11") (pintype "passive+no_connect"))
    )
    (net (code "79") (name "unconnected-(U1-PC5-Pad25)") (class "Default")
      (node (ref "U1") (pin "25") (pinfunction "PC5_25") (pintype "passive+no_connect"))
    )
    (net (code "80") (name "unconnected-(U1-PC6-Pad37)") (class "Default")
      (node (ref "U1") (pin "37") (pinfunction "PC6_37") (pintype "passive+no_connect"))
    )
    (net (code "81") (name "unconnected-(U1-PC8-Pad39)") (class "Default")
      (node (ref "U1") (pin "39") (pinfunction "PC8_39") (pintype "passive+no_connect"))
    )
    (net (code "82") (name "unconnected-(U4-CHRG-Pad1)") (class "Default")
      (node (ref "U4") (pin "1") (pinfunction "CHRG_1") (pintype "passive+no_connect"))
    )
  )
)
